# fpga-breakout.net
KiCad netlist of a schematic drawn in EAGLE
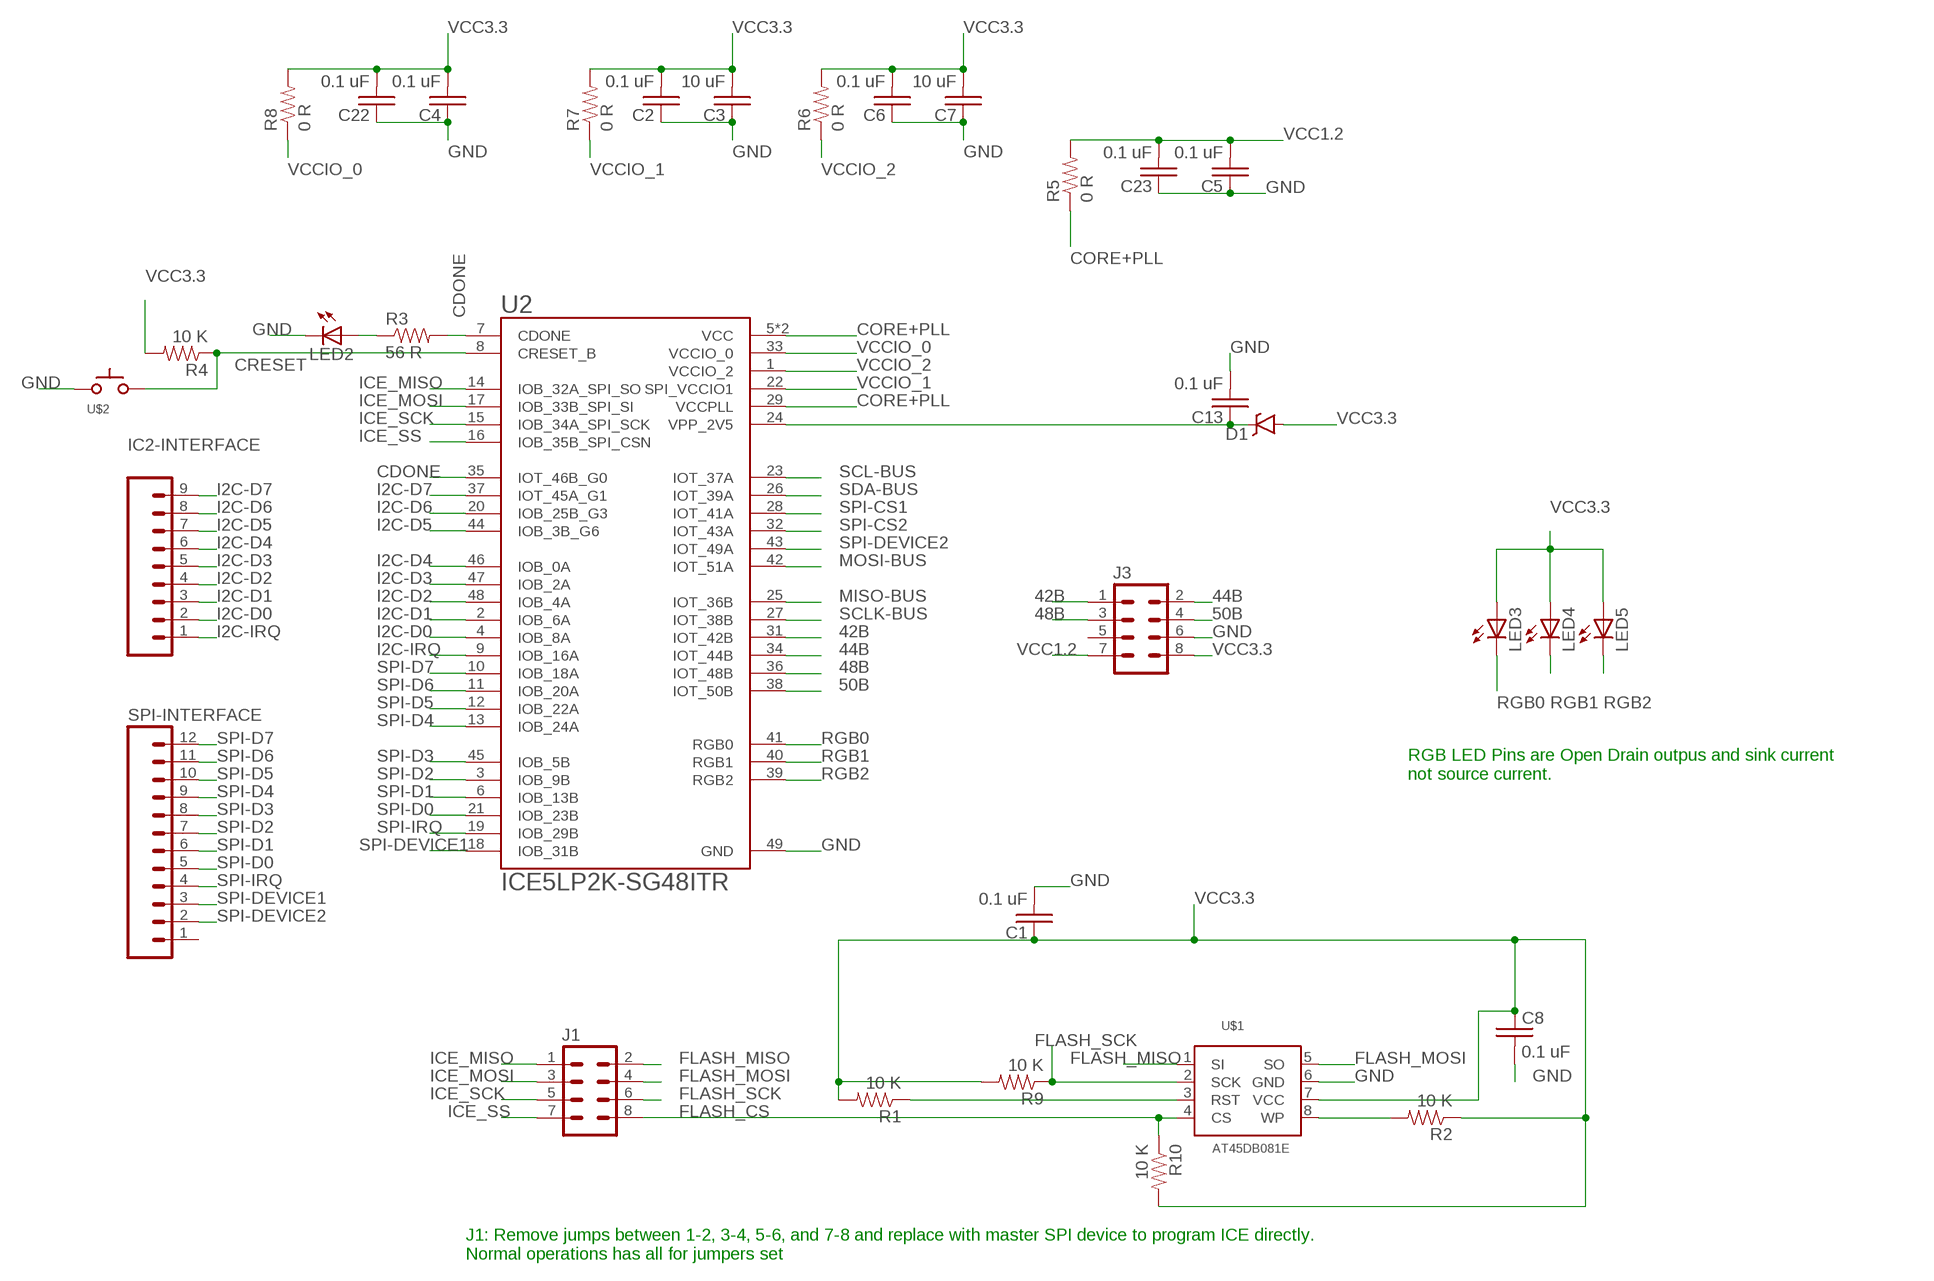
[diagram p0: schematic, sheet 1]
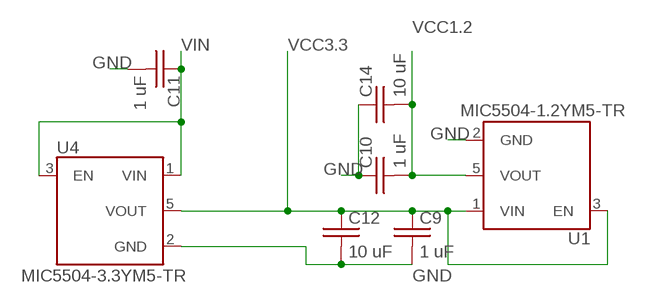
[diagram p1: schematic, sheet 2]
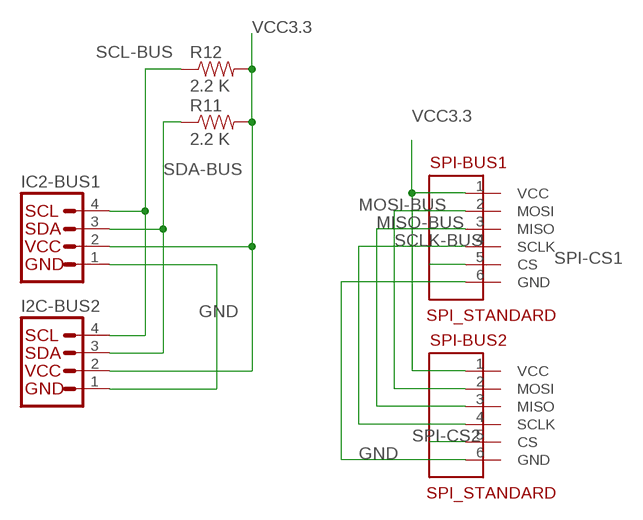
[diagram p2: schematic, sheet 3]

(export (version "E")
  (design (tool "Eeschema 10.0.6"))
  (components
    (comp (ref "I2C-BUS2")
      (value "I2C_STANDARD")
      (footprint "eagle-import:1X04")
      (libsource (lib "eagle-import") (part "I2C_STANDARD"))
    )
    (comp (ref "IC2-BUS1")
      (value "I2C_STANDARD")
      (footprint "eagle-import:1X04")
      (libsource (lib "eagle-import") (part "I2C_STANDARD"))
    )
    (comp (ref "R11")
      (value "2.2 K")
      (footprint "eagle-import:0805")
      (libsource (lib "eagle-import") (part "RESISTOR0805-RES"))
    )
    (comp (ref "R12")
      (value "2.2 K")
      (footprint "eagle-import:0805")
      (libsource (lib "eagle-import") (part "RESISTOR0805-RES"))
    )
    (comp (ref "SPI-BUS1")
      (value "SPI_STANDARD")
      (footprint "eagle-import:1X06")
      (libsource (lib "eagle-import") (part "SPI_STANDARD"))
    )
    (comp (ref "SPI-BUS2")
      (value "SPI_STANDARD")
      (footprint "eagle-import:1X06")
      (libsource (lib "eagle-import") (part "SPI_STANDARD"))
    )
    (comp (ref "C1")
      (value "0.1 uF")
      (footprint "eagle-import:C0603")
      (libsource (lib "eagle-import") (part "C-USC0603"))
    )
    (comp (ref "C2")
      (value "0.1 uF")
      (footprint "eagle-import:C0603")
      (libsource (lib "eagle-import") (part "C-USC0603"))
    )
    (comp (ref "C3")
      (value "10 uF")
      (footprint "eagle-import:C0603")
      (libsource (lib "eagle-import") (part "C-USC0603"))
    )
    (comp (ref "C4")
      (value "0.1 uF")
      (footprint "eagle-import:C0603")
      (libsource (lib "eagle-import") (part "C-USC0603"))
    )
    (comp (ref "C5")
      (value "0.1 uF")
      (footprint "eagle-import:C0603")
      (libsource (lib "eagle-import") (part "C-USC0603"))
    )
    (comp (ref "C6")
      (value "0.1 uF")
      (footprint "eagle-import:C0603")
      (libsource (lib "eagle-import") (part "C-USC0603"))
    )
    (comp (ref "C7")
      (value "10 uF")
      (footprint "eagle-import:C0603")
      (libsource (lib "eagle-import") (part "C-USC0603"))
    )
    (comp (ref "C8")
      (value "0.1 uF")
      (footprint "eagle-import:C0603")
      (libsource (lib "eagle-import") (part "C-USC0603"))
    )
    (comp (ref "C13")
      (value "0.1 uF")
      (footprint "eagle-import:C0603")
      (libsource (lib "eagle-import") (part "C-USC0603"))
    )
    (comp (ref "C22")
      (value "0.1 uF")
      (footprint "eagle-import:C0603")
      (libsource (lib "eagle-import") (part "C-USC0603"))
    )
    (comp (ref "C23")
      (value "0.1 uF")
      (footprint "eagle-import:C0603")
      (libsource (lib "eagle-import") (part "C-USC0603"))
    )
    (comp (ref "D1")
      (value "DIODE-SCHOTTKYDIOAD-TH")
      (footprint "eagle-import:DIOAD1060W80L520D270")
      (libsource (lib "eagle-import") (part "DIODE-SCHOTTKYDIOAD-TH"))
    )
    (comp (ref "IC2-INTERFACE")
      (value "M09")
      (footprint "eagle-import:1X09")
      (libsource (lib "eagle-import") (part "M09"))
    )
    (comp (ref "J1")
      (value "M04X2")
      (footprint "eagle-import:2X4")
      (libsource (lib "eagle-import") (part "M04X2"))
    )
    (comp (ref "J3")
      (value "M04X2")
      (footprint "eagle-import:2X4")
      (libsource (lib "eagle-import") (part "M04X2"))
    )
    (comp (ref "LED2")
      (value "LED1206")
      (footprint "eagle-import:LED-1206")
      (libsource (lib "eagle-import") (part "LED1206"))
    )
    (comp (ref "LED3")
      (value "LED3MM")
      (footprint "eagle-import:LED3MM")
      (libsource (lib "eagle-import") (part "LED3MM"))
    )
    (comp (ref "LED4")
      (value "LED3MM")
      (footprint "eagle-import:LED3MM")
      (libsource (lib "eagle-import") (part "LED3MM"))
    )
    (comp (ref "LED5")
      (value "LED3MM")
      (footprint "eagle-import:LED3MM")
      (libsource (lib "eagle-import") (part "LED3MM"))
    )
    (comp (ref "R1")
      (value "10 K")
      (footprint "eagle-import:0805")
      (libsource (lib "eagle-import") (part "RESISTOR0805-RES"))
    )
    (comp (ref "R2")
      (value "10 K")
      (footprint "eagle-import:0805")
      (libsource (lib "eagle-import") (part "RESISTOR0805-RES"))
    )
    (comp (ref "R3")
      (value "56 R")
      (footprint "eagle-import:1206")
      (libsource (lib "eagle-import") (part "RESISTOR1206"))
    )
    (comp (ref "R4")
      (value "10 K")
      (footprint "eagle-import:0805")
      (libsource (lib "eagle-import") (part "RESISTOR0805-RES"))
    )
    (comp (ref "R5")
      (value "0 R")
      (footprint "eagle-import:0805")
      (libsource (lib "eagle-import") (part "RESISTOR0805-RES"))
    )
    (comp (ref "R6")
      (value "0 R")
      (footprint "eagle-import:0805")
      (libsource (lib "eagle-import") (part "RESISTOR0805-RES"))
    )
    (comp (ref "R7")
      (value "0 R")
      (footprint "eagle-import:0805")
      (libsource (lib "eagle-import") (part "RESISTOR0805-RES"))
    )
    (comp (ref "R8")
      (value "0 R")
      (footprint "eagle-import:0805")
      (libsource (lib "eagle-import") (part "RESISTOR0805-RES"))
    )
    (comp (ref "R9")
      (value "10 K")
      (footprint "eagle-import:0805")
      (libsource (lib "eagle-import") (part "RESISTOR0805-RES"))
    )
    (comp (ref "R10")
      (value "10 K")
      (footprint "eagle-import:0805")
      (libsource (lib "eagle-import") (part "RESISTOR0805-RES"))
    )
    (comp (ref "SPI-INTERFACE")
      (value "M12PTH")
      (footprint "eagle-import:1X12")
      (libsource (lib "eagle-import") (part "M12PTH"))
    )
    (comp (ref "U$1")
      (value "AT45DB8081E")
      (footprint "eagle-import:SOIC127P600X175-8N")
      (libsource (lib "eagle-import") (part "AT45DB8081E"))
    )
    (comp (ref "U$2")
      (value "SWITCH_TACTILETACTILE-2PIN-NARROW")
      (footprint "eagle-import:TACTILE-2PIN-NARROW")
      (libsource (lib "eagle-import") (part "SWITCH_TACTILETACTILE-2PIN-NARROW"))
    )
    (comp (ref "U2")
      (value "ICE5LP2K-SG48ITR")
      (footprint "eagle-import:QFN50P700X700X100-49N")
      (fields
        (field (name "DIGI-KEY_PART_NUMBER") "220-2155-1-ND")
        (field (name "MF") "Lattice Semiconductor")
        (field (name "MP") "ICE5LP1K-SG48ITR")
      )
      (libsource (lib "eagle-import") (part "ICE5LP2K-SG48ITR"))
    )
    (comp (ref "C9")
      (value "1 uF")
      (footprint "eagle-import:C0603")
      (libsource (lib "eagle-import") (part "C-USC0603"))
    )
    (comp (ref "C10")
      (value "1 uF")
      (footprint "eagle-import:C0603")
      (libsource (lib "eagle-import") (part "C-USC0603"))
    )
    (comp (ref "C11")
      (value "1 uF")
      (footprint "eagle-import:C0603")
      (libsource (lib "eagle-import") (part "C-USC0603"))
    )
    (comp (ref "C12")
      (value "10 uF")
      (footprint "eagle-import:C0603")
      (libsource (lib "eagle-import") (part "C-USC0603"))
    )
    (comp (ref "C14")
      (value "10 uF")
      (footprint "eagle-import:C0603")
      (libsource (lib "eagle-import") (part "C-USC0603"))
    )
    (comp (ref "U1")
      (value "MIC5504-1.2YM5-TR")
      (footprint "eagle-import:SOT23-5P95_280X145XL45X37N")
      (fields (field (name "MF") "Microchip"))
      (libsource (lib "eagle-import") (part "MIC5504-1.2YM5-TR"))
    )
    (comp (ref "U4")
      (value "MIC5504-3.3YM5-TR")
      (footprint "eagle-import:SOT23-5P95_280X145XL45X37N")
      (fields (field (name "MF") "Microchip") (field (name "MP") "MIC5504-1.2YM5-TR"))
      (libsource (lib "eagle-import") (part "MIC5504-3.3YM5-TR"))
    )
  )
  (nets
    (net (code "1") (name "42B") (class "Default")
      (node (ref "J3") (pin "1") (pinfunction "1_1") (pintype "passive"))
      (node (ref "U2") (pin "31") (pinfunction "IOT_42B_31") (pintype "bidirectional"))
    )
    (net (code "2") (name "44B") (class "Default")
      (node (ref "J3") (pin "2") (pinfunction "2_2") (pintype "passive"))
      (node (ref "U2") (pin "34") (pinfunction "IOT_44B_34") (pintype "bidirectional"))
    )
    (net (code "3") (name "48B") (class "Default")
      (node (ref "J3") (pin "3") (pinfunction "3_3") (pintype "passive"))
      (node (ref "U2") (pin "36") (pinfunction "IOT_48B_36") (pintype "bidirectional"))
    )
    (net (code "4") (name "50B") (class "Default")
      (node (ref "J3") (pin "4") (pinfunction "4_4") (pintype "passive"))
      (node (ref "U2") (pin "38") (pinfunction "IOT_50B_38") (pintype "bidirectional"))
    )
    (net (code "5") (name "CDONE") (class "Default")
      (node (ref "R3") (pin "2") (pinfunction "2_2") (pintype "passive"))
      (node (ref "U2") (pin "35") (pinfunction "IOT_46B_G0_35") (pintype "bidirectional"))
      (node (ref "U2") (pin "7") (pinfunction "CDONE_7") (pintype "input"))
    )
    (net (code "6") (name "CORE+PLL") (class "Default")
      (node (ref "R5") (pin "1") (pinfunction "1_1") (pintype "passive"))
      (node (ref "U2") (pin "29") (pinfunction "VCCPLL_29") (pintype "power_in"))
      (node (ref "U2") (pin "30") (pinfunction "VCC_30") (pintype "power_in"))
      (node (ref "U2") (pin "5") (pinfunction "VCC_5") (pintype "power_in"))
    )
    (net (code "7") (name "CRESET") (class "Default")
      (node (ref "R4") (pin "1") (pinfunction "1_1") (pintype "passive"))
      (node (ref "U$2") (pin "P$1") (pinfunction "A_P$1") (pintype "passive"))
      (node (ref "U2") (pin "8") (pinfunction "CRESET_B_8") (pintype "input"))
    )
    (net (code "8") (name "FLASH_CS") (class "Default")
      (node (ref "J1") (pin "8") (pinfunction "8_8") (pintype "passive"))
      (node (ref "R10") (pin "1") (pinfunction "1_1") (pintype "passive"))
      (node (ref "U$1") (pin "4") (pinfunction "CS_4") (pintype "bidirectional"))
    )
    (net (code "9") (name "FLASH_MISO") (class "Default")
      (node (ref "J1") (pin "2") (pinfunction "2_2") (pintype "passive"))
      (node (ref "U$1") (pin "1") (pinfunction "SI_1") (pintype "bidirectional"))
    )
    (net (code "10") (name "FLASH_MOSI") (class "Default")
      (node (ref "J1") (pin "4") (pinfunction "4_4") (pintype "passive"))
      (node (ref "U$1") (pin "5") (pinfunction "SO_5") (pintype "bidirectional"))
    )
    (net (code "11") (name "FLASH_SCK") (class "Default")
      (node (ref "J1") (pin "6") (pinfunction "6_6") (pintype "passive"))
      (node (ref "R9") (pin "1") (pinfunction "1_1") (pintype "passive"))
      (node (ref "U$1") (pin "2") (pinfunction "SCK_2") (pintype "bidirectional"))
    )
    (net (code "12") (name "GND") (class "Default")
      (node (ref "C1") (pin "2") (pinfunction "2_2") (pintype "passive"))
      (node (ref "C10") (pin "1") (pinfunction "1_1") (pintype "passive"))
      (node (ref "C11") (pin "2") (pinfunction "2_2") (pintype "passive"))
      (node (ref "C12") (pin "2") (pinfunction "2_2") (pintype "passive"))
      (node (ref "C13") (pin "2") (pinfunction "2_2") (pintype "passive"))
      (node (ref "C14") (pin "1") (pinfunction "1_1") (pintype "passive"))
      (node (ref "C2") (pin "1") (pinfunction "1_1") (pintype "passive"))
      (node (ref "C22") (pin "1") (pinfunction "1_1") (pintype "passive"))
      (node (ref "C23") (pin "1") (pinfunction "1_1") (pintype "passive"))
      (node (ref "C3") (pin "1") (pinfunction "1_1") (pintype "passive"))
      (node (ref "C4") (pin "1") (pinfunction "1_1") (pintype "passive"))
      (node (ref "C5") (pin "1") (pinfunction "1_1") (pintype "passive"))
      (node (ref "C6") (pin "1") (pinfunction "1_1") (pintype "passive"))
      (node (ref "C7") (pin "1") (pinfunction "1_1") (pintype "passive"))
      (node (ref "C8") (pin "2") (pinfunction "2_2") (pintype "passive"))
      (node (ref "C9") (pin "2") (pinfunction "2_2") (pintype "passive"))
      (node (ref "I2C-BUS2") (pin "1") (pinfunction "1_1") (pintype "passive"))
      (node (ref "IC2-BUS1") (pin "1") (pinfunction "1_1") (pintype "passive"))
      (node (ref "J3") (pin "6") (pinfunction "6_6") (pintype "passive"))
      (node (ref "LED2") (pin "C") (pinfunction "C_C") (pintype "output"))
      (node (ref "SPI-BUS1") (pin "6") (pinfunction "GND_6") (pintype "power_in"))
      (node (ref "SPI-BUS2") (pin "6") (pinfunction "GND_6") (pintype "power_in"))
      (node (ref "U$1") (pin "6") (pinfunction "GND_6") (pintype "bidirectional"))
      (node (ref "U$2") (pin "P$2") (pinfunction "C_P$2") (pintype "passive"))
      (node (ref "U1") (pin "2") (pinfunction "GND_2") (pintype "power_in"))
      (node (ref "U2") (pin "49") (pinfunction "GND_49") (pintype "power_in"))
      (node (ref "U4") (pin "2") (pinfunction "GND_2") (pintype "power_in"))
    )
    (net (code "13") (name "I2C-D0") (class "Default")
      (node (ref "IC2-INTERFACE") (pin "2") (pinfunction "2_2") (pintype "passive"))
      (node (ref "U2") (pin "4") (pinfunction "IOB_8A_4") (pintype "bidirectional"))
    )
    (net (code "14") (name "I2C-D1") (class "Default")
      (node (ref "IC2-INTERFACE") (pin "3") (pinfunction "3_3") (pintype "passive"))
      (node (ref "U2") (pin "2") (pinfunction "IOB_6A_2") (pintype "bidirectional"))
    )
    (net (code "15") (name "I2C-D2") (class "Default")
      (node (ref "IC2-INTERFACE") (pin "4") (pinfunction "4_4") (pintype "passive"))
      (node (ref "U2") (pin "48") (pinfunction "IOB_4A_48") (pintype "bidirectional"))
    )
    (net (code "16") (name "I2C-D3") (class "Default")
      (node (ref "IC2-INTERFACE") (pin "5") (pinfunction "5_5") (pintype "passive"))
      (node (ref "U2") (pin "47") (pinfunction "IOB_2A_47") (pintype "bidirectional"))
    )
    (net (code "17") (name "I2C-D4") (class "Default")
      (node (ref "IC2-INTERFACE") (pin "6") (pinfunction "6_6") (pintype "passive"))
      (node (ref "U2") (pin "46") (pinfunction "IOB_0A_46") (pintype "bidirectional"))
    )
    (net (code "18") (name "I2C-D5") (class "Default")
      (node (ref "IC2-INTERFACE") (pin "7") (pinfunction "7_7") (pintype "passive"))
      (node (ref "U2") (pin "44") (pinfunction "IOB_3B_G6_44") (pintype "bidirectional"))
    )
    (net (code "19") (name "I2C-D6") (class "Default")
      (node (ref "IC2-INTERFACE") (pin "8") (pinfunction "8_8") (pintype "passive"))
      (node (ref "U2") (pin "20") (pinfunction "IOB_25B_G3_20") (pintype "bidirectional"))
    )
    (net (code "20") (name "I2C-D7") (class "Default")
      (node (ref "IC2-INTERFACE") (pin "9") (pinfunction "9_9") (pintype "passive"))
      (node (ref "U2") (pin "37") (pinfunction "IOT_45A_G1_37") (pintype "bidirectional"))
    )
    (net (code "21") (name "I2C-IRQ") (class "Default")
      (node (ref "IC2-INTERFACE") (pin "1") (pinfunction "1_1") (pintype "passive"))
      (node (ref "U2") (pin "9") (pinfunction "IOB_16A_9") (pintype "bidirectional"))
    )
    (net (code "22") (name "ICE_MISO") (class "Default")
      (node (ref "J1") (pin "1") (pinfunction "1_1") (pintype "passive"))
      (node (ref "U2") (pin "14") (pinfunction "IOB_32A_SPI_SO_14") (pintype "bidirectional"))
    )
    (net (code "23") (name "ICE_MOSI") (class "Default")
      (node (ref "J1") (pin "3") (pinfunction "3_3") (pintype "passive"))
      (node (ref "U2") (pin "17") (pinfunction "IOB_33B_SPI_SI_17") (pintype "bidirectional"))
    )
    (net (code "24") (name "ICE_SCK") (class "Default")
      (node (ref "J1") (pin "5") (pinfunction "5_5") (pintype "passive"))
      (node (ref "U2") (pin "15") (pinfunction "IOB_34A_SPI_SCK_15") (pintype "bidirectional"))
    )
    (net (code "25") (name "ICE_SS") (class "Default")
      (node (ref "J1") (pin "7") (pinfunction "7_7") (pintype "passive"))
      (node (ref "U2") (pin "16") (pinfunction "IOB_35B_SPI_CSN_16") (pintype "bidirectional"))
    )
    (net (code "26") (name "MISO-BUS") (class "Default")
      (node (ref "SPI-BUS1") (pin "3") (pinfunction "MISO_3") (pintype "bidirectional"))
      (node (ref "SPI-BUS2") (pin "3") (pinfunction "MISO_3") (pintype "bidirectional"))
      (node (ref "U2") (pin "25") (pinfunction "IOT_36B_25") (pintype "bidirectional"))
    )
    (net (code "27") (name "MOSI-BUS") (class "Default")
      (node (ref "SPI-BUS1") (pin "2") (pinfunction "MOSI_2") (pintype "bidirectional"))
      (node (ref "SPI-BUS2") (pin "2") (pinfunction "MOSI_2") (pintype "bidirectional"))
      (node (ref "U2") (pin "42") (pinfunction "IOT_51A_42") (pintype "bidirectional"))
    )
    (net (code "28") (name "Net-(LED2-PadA)") (class "Default")
      (node (ref "LED2") (pin "A") (pinfunction "A_A") (pintype "input"))
      (node (ref "R3") (pin "1") (pinfunction "1_1") (pintype "passive"))
    )
    (net (code "29") (name "Net-(U$1-RST)") (class "Default")
      (node (ref "R1") (pin "1") (pinfunction "1_1") (pintype "passive"))
      (node (ref "U$1") (pin "3") (pinfunction "RST_3") (pintype "bidirectional"))
    )
    (net (code "30") (name "Net-(U$1-WP)") (class "Default")
      (node (ref "R2") (pin "2") (pinfunction "2_2") (pintype "passive"))
      (node (ref "U$1") (pin "8") (pinfunction "WP_8") (pintype "bidirectional"))
    )
    (net (code "31") (name "Net-(U2-VPP_2V5)") (class "Default")
      (node (ref "C13") (pin "1") (pinfunction "1_1") (pintype "passive"))
      (node (ref "D1") (pin "C") (pinfunction "C_C") (pintype "passive"))
      (node (ref "U2") (pin "24") (pinfunction "VPP_2V5_24") (pintype "power_in"))
    )
    (net (code "32") (name "RGB0") (class "Default")
      (node (ref "LED3") (pin "K") (pinfunction "C_K") (pintype "output"))
      (node (ref "U2") (pin "41") (pinfunction "RGB0_41") (pintype "passive"))
    )
    (net (code "33") (name "RGB1") (class "Default")
      (node (ref "LED4") (pin "K") (pinfunction "C_K") (pintype "output"))
      (node (ref "U2") (pin "40") (pinfunction "RGB1_40") (pintype "passive"))
    )
    (net (code "34") (name "RGB2") (class "Default")
      (node (ref "LED5") (pin "K") (pinfunction "C_K") (pintype "output"))
      (node (ref "U2") (pin "39") (pinfunction "RGB2_39") (pintype "passive"))
    )
    (net (code "35") (name "SCL-BUS") (class "Default")
      (node (ref "I2C-BUS2") (pin "4") (pinfunction "4_4") (pintype "passive"))
      (node (ref "IC2-BUS1") (pin "4") (pinfunction "4_4") (pintype "passive"))
      (node (ref "R12") (pin "1") (pinfunction "1_1") (pintype "passive"))
      (node (ref "U2") (pin "23") (pinfunction "IOT_37A_23") (pintype "bidirectional"))
    )
    (net (code "36") (name "SCLK-BUS") (class "Default")
      (node (ref "SPI-BUS1") (pin "4") (pinfunction "SCLK_4") (pintype "bidirectional"))
      (node (ref "SPI-BUS2") (pin "4") (pinfunction "SCLK_4") (pintype "bidirectional"))
      (node (ref "U2") (pin "27") (pinfunction "IOT_38B_27") (pintype "bidirectional"))
    )
    (net (code "37") (name "SDA-BUS") (class "Default")
      (node (ref "I2C-BUS2") (pin "3") (pinfunction "3_3") (pintype "passive"))
      (node (ref "IC2-BUS1") (pin "3") (pinfunction "3_3") (pintype "passive"))
      (node (ref "R11") (pin "1") (pinfunction "1_1") (pintype "passive"))
      (node (ref "U2") (pin "26") (pinfunction "IOT_39A_26") (pintype "bidirectional"))
    )
    (net (code "38") (name "SPI-CS1") (class "Default")
      (node (ref "SPI-BUS1") (pin "5") (pinfunction "CS_5") (pintype "bidirectional"))
      (node (ref "U2") (pin "28") (pinfunction "IOT_41A_28") (pintype "bidirectional"))
    )
    (net (code "39") (name "SPI-CS2") (class "Default")
      (node (ref "SPI-BUS2") (pin "5") (pinfunction "CS_5") (pintype "bidirectional"))
      (node (ref "U2") (pin "32") (pinfunction "IOT_43A_32") (pintype "bidirectional"))
    )
    (net (code "40") (name "SPI-D0") (class "Default")
      (node (ref "SPI-INTERFACE") (pin "5") (pinfunction "5_5") (pintype "passive"))
      (node (ref "U2") (pin "21") (pinfunction "IOB_23B_21") (pintype "bidirectional"))
    )
    (net (code "41") (name "SPI-D1") (class "Default")
      (node (ref "SPI-INTERFACE") (pin "6") (pinfunction "6_6") (pintype "passive"))
      (node (ref "U2") (pin "6") (pinfunction "IOB_13B_6") (pintype "bidirectional"))
    )
    (net (code "42") (name "SPI-D2") (class "Default")
      (node (ref "SPI-INTERFACE") (pin "7") (pinfunction "7_7") (pintype "passive"))
      (node (ref "U2") (pin "3") (pinfunction "IOB_9B_3") (pintype "bidirectional"))
    )
    (net (code "43") (name "SPI-D3") (class "Default")
      (node (ref "SPI-INTERFACE") (pin "8") (pinfunction "8_8") (pintype "passive"))
      (node (ref "U2") (pin "45") (pinfunction "IOB_5B_45") (pintype "bidirectional"))
    )
    (net (code "44") (name "SPI-D4") (class "Default")
      (node (ref "SPI-INTERFACE") (pin "9") (pinfunction "9_9") (pintype "passive"))
      (node (ref "U2") (pin "13") (pinfunction "IOB_24A_13") (pintype "bidirectional"))
    )
    (net (code "45") (name "SPI-D5") (class "Default")
      (node (ref "SPI-INTERFACE") (pin "10") (pinfunction "10_10") (pintype "passive"))
      (node (ref "U2") (pin "12") (pinfunction "IOB_22A_12") (pintype "bidirectional"))
    )
    (net (code "46") (name "SPI-D6") (class "Default")
      (node (ref "SPI-INTERFACE") (pin "11") (pinfunction "11_11") (pintype "passive"))
      (node (ref "U2") (pin "11") (pinfunction "IOB_20A_11") (pintype "bidirectional"))
    )
    (net (code "47") (name "SPI-D7") (class "Default")
      (node (ref "SPI-INTERFACE") (pin "12") (pinfunction "12_12") (pintype "passive"))
      (node (ref "U2") (pin "10") (pinfunction "IOB_18A_10") (pintype "bidirectional"))
    )
    (net (code "48") (name "SPI-DEVICE1") (class "Default")
      (node (ref "SPI-INTERFACE") (pin "3") (pinfunction "3_3") (pintype "passive"))
      (node (ref "U2") (pin "18") (pinfunction "IOB_31B_18") (pintype "bidirectional"))
    )
    (net (code "49") (name "SPI-DEVICE2") (class "Default")
      (node (ref "SPI-INTERFACE") (pin "2") (pinfunction "2_2") (pintype "passive"))
      (node (ref "U2") (pin "43") (pinfunction "IOT_49A_43") (pintype "bidirectional"))
    )
    (net (code "50") (name "SPI-IRQ") (class "Default")
      (node (ref "SPI-INTERFACE") (pin "4") (pinfunction "4_4") (pintype "passive"))
      (node (ref "U2") (pin "19") (pinfunction "IOB_29B_19") (pintype "bidirectional"))
    )
    (net (code "51") (name "VCC1.2") (class "Default")
      (node (ref "C10") (pin "2") (pinfunction "2_2") (pintype "passive"))
      (node (ref "C14") (pin "2") (pinfunction "2_2") (pintype "passive"))
      (node (ref "C23") (pin "2") (pinfunction "2_2") (pintype "passive"))
      (node (ref "C5") (pin "2") (pinfunction "2_2") (pintype "passive"))
      (node (ref "J3") (pin "7") (pinfunction "7_7") (pintype "passive"))
      (node (ref "R5") (pin "2") (pinfunction "2_2") (pintype "passive"))
      (node (ref "U1") (pin "5") (pinfunction "VOUT_5") (pintype "output"))
    )
    (net (code "52") (name "VCC3.3") (class "Default")
      (node (ref "C1") (pin "1") (pinfunction "1_1") (pintype "passive"))
      (node (ref "C12") (pin "1") (pinfunction "1_1") (pintype "passive"))
      (node (ref "C2") (pin "2") (pinfunction "2_2") (pintype "passive"))
      (node (ref "C22") (pin "2") (pinfunction "2_2") (pintype "passive"))
      (node (ref "C3") (pin "2") (pinfunction "2_2") (pintype "passive"))
      (node (ref "C4") (pin "2") (pinfunction "2_2") (pintype "passive"))
      (node (ref "C6") (pin "2") (pinfunction "2_2") (pintype "passive"))
      (node (ref "C7") (pin "2") (pinfunction "2_2") (pintype "passive"))
      (node (ref "C8") (pin "1") (pinfunction "1_1") (pintype "passive"))
      (node (ref "C9") (pin "1") (pinfunction "1_1") (pintype "passive"))
      (node (ref "D1") (pin "A") (pinfunction "A_A") (pintype "passive"))
      (node (ref "I2C-BUS2") (pin "2") (pinfunction "2_2") (pintype "passive"))
      (node (ref "IC2-BUS1") (pin "2") (pinfunction "2_2") (pintype "passive"))
      (node (ref "J3") (pin "8") (pinfunction "8_8") (pintype "passive"))
      (node (ref "LED3") (pin "A") (pinfunction "A_A") (pintype "input"))
      (node (ref "LED4") (pin "A") (pinfunction "A_A") (pintype "input"))
      (node (ref "LED5") (pin "A") (pinfunction "A_A") (pintype "input"))
      (node (ref "R1") (pin "2") (pinfunction "2_2") (pintype "passive"))
      (node (ref "R10") (pin "2") (pinfunction "2_2") (pintype "passive"))
      (node (ref "R11") (pin "2") (pinfunction "2_2") (pintype "passive"))
      (node (ref "R12") (pin "2") (pinfunction "2_2") (pintype "passive"))
      (node (ref "R2") (pin "1") (pinfunction "1_1") (pintype "passive"))
      (node (ref "R4") (pin "2") (pinfunction "2_2") (pintype "passive"))
      (node (ref "R6") (pin "2") (pinfunction "2_2") (pintype "passive"))
      (node (ref "R7") (pin "2") (pinfunction "2_2") (pintype "passive"))
      (node (ref "R8") (pin "2") (pinfunction "2_2") (pintype "passive"))
      (node (ref "R9") (pin "2") (pinfunction "2_2") (pintype "passive"))
      (node (ref "SPI-BUS1") (pin "1") (pinfunction "VCC_1") (pintype "power_in"))
      (node (ref "SPI-BUS2") (pin "1") (pinfunction "VCC_1") (pintype "power_in"))
      (node (ref "U$1") (pin "7") (pinfunction "VCC_7") (pintype "bidirectional"))
      (node (ref "U1") (pin "1") (pinfunction "VIN_1") (pintype "power_in"))
      (node (ref "U1") (pin "3") (pinfunction "EN_3") (pintype "input"))
      (node (ref "U4") (pin "5") (pinfunction "VOUT_5") (pintype "output"))
    )
    (net (code "53") (name "VCCIO_0") (class "Default")
      (node (ref "R8") (pin "1") (pinfunction "1_1") (pintype "passive"))
      (node (ref "U2") (pin "33") (pinfunction "VCCIO_0_33") (pintype "power_in"))
    )
    (net (code "54") (name "VCCIO_1") (class "Default")
      (node (ref "R7") (pin "1") (pinfunction "1_1") (pintype "passive"))
      (node (ref "U2") (pin "22") (pinfunction "SPI_VCCIO1_22") (pintype "power_in"))
    )
    (net (code "55") (name "VCCIO_2") (class "Default")
      (node (ref "R6") (pin "1") (pinfunction "1_1") (pintype "passive"))
      (node (ref "U2") (pin "1") (pinfunction "VCCIO_2_1") (pintype "power_in"))
    )
    (net (code "56") (name "VIN") (class "Default")
      (node (ref "C11") (pin "1") (pinfunction "1_1") (pintype "passive"))
      (node (ref "U4") (pin "1") (pinfunction "VIN_1") (pintype "power_in"))
      (node (ref "U4") (pin "3") (pinfunction "EN_3") (pintype "input"))
    )
    (net (code "57") (name "unconnected-(J3-Pad5)") (class "Default")
      (node (ref "J3") (pin "5") (pinfunction "5_5") (pintype "passive"))
    )
    (net (code "58") (name "unconnected-(SPI-INTERFACE-Pad1)") (class "Default")
      (node (ref "SPI-INTERFACE") (pin "1") (pinfunction "1_1") (pintype "passive"))
    )
  )
)
